# USBC_BREAKOUT.net
KiCad netlist of a schematic drawn in Altium Designer
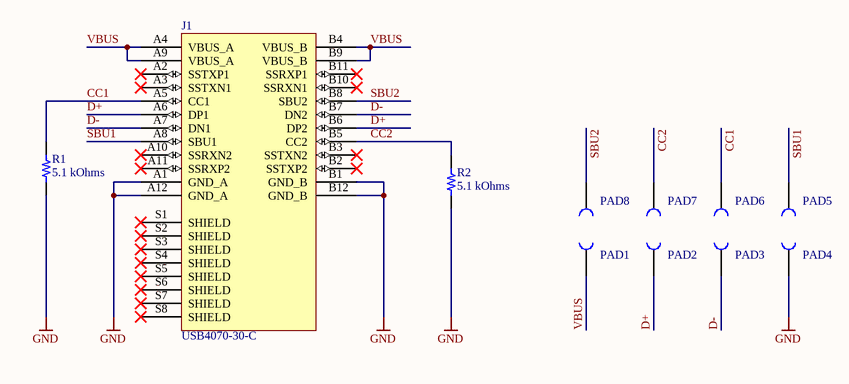
[diagram p0: USBC_BREAKOUT.SchDoc]

(export (version "E")
  (design (tool "Eeschema 10.0.6"))
  (components
    (comp (ref "J1")
      (value "USB4070-30-C")
      (footprint "GCT_USB4070-30-C_REVC5")
      (fields (field (name "MF") "Global Connector Technology"))
      (libsource (lib "LabratsSynthLib") (part "USB4070-30-C"))
    )
    (comp (ref "PAD1")
      (value "CastellatedPad")
      (footprint "CastellatedPad")
      (description "Castellated Pad")
      (libsource (lib "LabratsSynthLib") (part "CastellatedPad"))
    )
    (comp (ref "PAD2")
      (value "CastellatedPad")
      (footprint "CastellatedPad")
      (description "Castellated Pad")
      (libsource (lib "LabratsSynthLib") (part "CastellatedPad"))
    )
    (comp (ref "PAD3")
      (value "CastellatedPad")
      (footprint "CastellatedPad")
      (description "Castellated Pad")
      (libsource (lib "LabratsSynthLib") (part "CastellatedPad"))
    )
    (comp (ref "PAD4")
      (value "CastellatedPad")
      (footprint "CastellatedPad")
      (description "Castellated Pad")
      (libsource (lib "LabratsSynthLib") (part "CastellatedPad"))
    )
    (comp (ref "PAD5")
      (value "CastellatedPad")
      (footprint "CastellatedPad")
      (description "Castellated Pad")
      (libsource (lib "LabratsSynthLib") (part "CastellatedPad"))
    )
    (comp (ref "PAD6")
      (value "CastellatedPad")
      (footprint "CastellatedPad")
      (description "Castellated Pad")
      (libsource (lib "LabratsSynthLib") (part "CastellatedPad"))
    )
    (comp (ref "PAD7")
      (value "CastellatedPad")
      (footprint "CastellatedPad")
      (description "Castellated Pad")
      (libsource (lib "LabratsSynthLib") (part "CastellatedPad"))
    )
    (comp (ref "PAD8")
      (value "CastellatedPad")
      (footprint "CastellatedPad")
      (description "Castellated Pad")
      (libsource (lib "LabratsSynthLib") (part "CastellatedPad"))
    )
    (comp (ref "R1")
      (value "5.1 kOhms")
      (footprint "RES 0603_1608")
      (description "RES SMD 5.1K OHM 1% 1/10W 0603")
      (fields (field (name "PART NUMBER") "CRCW06035K10FKEA") (field (name "MANUFACTURER") "Vishay Dale"))
      (libsource (lib "Celestial Altium Library") (part "Resistor"))
    )
    (comp (ref "R2")
      (value "5.1 kOhms")
      (footprint "RES 0603_1608")
      (description "RES SMD 5.1K OHM 1% 1/10W 0603")
      (fields (field (name "PART NUMBER") "CRCW06035K10FKEA") (field (name "MANUFACTURER") "Vishay Dale"))
      (libsource (lib "Celestial Altium Library") (part "Resistor"))
    )
  )
  (nets
    (net (code "1") (name "/CC1") (class "Default")
      (node (ref "J1") (pin "A5") (pinfunction "CC1_A5") (pintype "bidirectional"))
      (node (ref "PAD6") (pin "0") (pinfunction "0_0") (pintype "passive"))
      (node (ref "R1") (pin "2") (pinfunction "2_2") (pintype "passive"))
    )
    (net (code "2") (name "/CC2") (class "Default")
      (node (ref "J1") (pin "B5") (pinfunction "CC2_B5") (pintype "bidirectional"))
      (node (ref "PAD7") (pin "0") (pinfunction "0_0") (pintype "passive"))
      (node (ref "R2") (pin "2") (pinfunction "2_2") (pintype "passive"))
    )
    (net (code "3") (name "/D+") (class "Default")
      (node (ref "J1") (pin "A6") (pinfunction "DP1_A6") (pintype "bidirectional"))
      (node (ref "J1") (pin "B6") (pinfunction "DP2_B6") (pintype "bidirectional"))
      (node (ref "PAD2") (pin "0") (pinfunction "0_0") (pintype "passive"))
    )
    (net (code "4") (name "/D-") (class "Default")
      (node (ref "J1") (pin "A7") (pinfunction "DN1_A7") (pintype "bidirectional"))
      (node (ref "J1") (pin "B7") (pinfunction "DN2_B7") (pintype "bidirectional"))
      (node (ref "PAD3") (pin "0") (pinfunction "0_0") (pintype "passive"))
    )
    (net (code "5") (name "/SBU1") (class "Default")
      (node (ref "J1") (pin "A8") (pinfunction "SBU1_A8") (pintype "bidirectional"))
      (node (ref "PAD5") (pin "0") (pinfunction "0_0") (pintype "passive"))
    )
    (net (code "6") (name "/SBU2") (class "Default")
      (node (ref "J1") (pin "B8") (pinfunction "SBU2_B8") (pintype "bidirectional"))
      (node (ref "PAD8") (pin "0") (pinfunction "0_0") (pintype "passive"))
    )
    (net (code "7") (name "/VBUS") (class "Default")
      (node (ref "J1") (pin "A4") (pinfunction "VBUS_A_A4") (pintype "power_in"))
      (node (ref "J1") (pin "A9") (pinfunction "VBUS_A_A9") (pintype "power_in"))
      (node (ref "J1") (pin "B4") (pinfunction "VBUS_B_B4") (pintype "power_in"))
      (node (ref "J1") (pin "B9") (pinfunction "VBUS_B_B9") (pintype "power_in"))
      (node (ref "PAD1") (pin "0") (pinfunction "0_0") (pintype "passive"))
    )
    (net (code "8") (name "GND") (class "Default")
      (node (ref "J1") (pin "A1") (pinfunction "GND_A_A1") (pintype "power_in"))
      (node (ref "J1") (pin "A12") (pinfunction "GND_A_A12") (pintype "power_in"))
      (node (ref "J1") (pin "B1") (pinfunction "GND_B_B1") (pintype "power_in"))
      (node (ref "J1") (pin "B12") (pinfunction "GND_B_B12") (pintype "power_in"))
      (node (ref "PAD4") (pin "0") (pinfunction "0_0") (pintype "passive"))
      (node (ref "R1") (pin "1") (pinfunction "1_1") (pintype "passive"))
      (node (ref "R2") (pin "1") (pinfunction "1_1") (pintype "passive"))
    )
    (net (code "9") (name "unconnected-(J1-SHIELD-PadS1)") (class "Default")
      (node (ref "J1") (pin "S1") (pinfunction "SHIELD_S1") (pintype "passive+no_connect"))
    )
    (net (code "10") (name "unconnected-(J1-SHIELD-PadS2)") (class "Default")
      (node (ref "J1") (pin "S2") (pinfunction "SHIELD_S2") (pintype "passive+no_connect"))
    )
    (net (code "11") (name "unconnected-(J1-SHIELD-PadS3)") (class "Default")
      (node (ref "J1") (pin "S3") (pinfunction "SHIELD_S3") (pintype "passive+no_connect"))
    )
    (net (code "12") (name "unconnected-(J1-SHIELD-PadS4)") (class "Default")
      (node (ref "J1") (pin "S4") (pinfunction "SHIELD_S4") (pintype "passive+no_connect"))
    )
    (net (code "13") (name "unconnected-(J1-SHIELD-PadS5)") (class "Default")
      (node (ref "J1") (pin "S5") (pinfunction "SHIELD_S5") (pintype "passive+no_connect"))
    )
    (net (code "14") (name "unconnected-(J1-SHIELD-PadS6)") (class "Default")
      (node (ref "J1") (pin "S6") (pinfunction "SHIELD_S6") (pintype "passive+no_connect"))
    )
    (net (code "15") (name "unconnected-(J1-SHIELD-PadS7)") (class "Default")
      (node (ref "J1") (pin "S7") (pinfunction "SHIELD_S7") (pintype "passive+no_connect"))
    )
    (net (code "16") (name "unconnected-(J1-SHIELD-PadS8)") (class "Default")
      (node (ref "J1") (pin "S8") (pinfunction "SHIELD_S8") (pintype "passive+no_connect"))
    )
    (net (code "17") (name "unconnected-(J1-SSRXN1-PadB10)") (class "Default")
      (node (ref "J1") (pin "B10") (pinfunction "SSRXN1_B10") (pintype "bidirectional+no_connect"))
    )
    (net (code "18") (name "unconnected-(J1-SSRXN2-PadA10)") (class "Default")
      (node (ref "J1") (pin "A10") (pinfunction "SSRXN2_A10") (pintype "bidirectional+no_connect"))
    )
    (net (code "19") (name "unconnected-(J1-SSRXP1-PadB11)") (class "Default")
      (node (ref "J1") (pin "B11") (pinfunction "SSRXP1_B11") (pintype "bidirectional+no_connect"))
    )
    (net (code "20") (name "unconnected-(J1-SSRXP2-PadA11)") (class "Default")
      (node (ref "J1") (pin "A11") (pinfunction "SSRXP2_A11") (pintype "bidirectional+no_connect"))
    )
    (net (code "21") (name "unconnected-(J1-SSTXN1-PadA3)") (class "Default")
      (node (ref "J1") (pin "A3") (pinfunction "SSTXN1_A3") (pintype "bidirectional+no_connect"))
    )
    (net (code "22") (name "unconnected-(J1-SSTXN2-PadB3)") (class "Default")
      (node (ref "J1") (pin "B3") (pinfunction "SSTXN2_B3") (pintype "bidirectional+no_connect"))
    )
    (net (code "23") (name "unconnected-(J1-SSTXP1-PadA2)") (class "Default")
      (node (ref "J1") (pin "A2") (pinfunction "SSTXP1_A2") (pintype "bidirectional+no_connect"))
    )
    (net (code "24") (name "unconnected-(J1-SSTXP2-PadB2)") (class "Default")
      (node (ref "J1") (pin "B2") (pinfunction "SSTXP2_B2") (pintype "bidirectional+no_connect"))
    )
  )
)
